# Blackbox_Brightness_Sensor_Schematic.net
KiCad netlist of a schematic drawn in Altium Designer
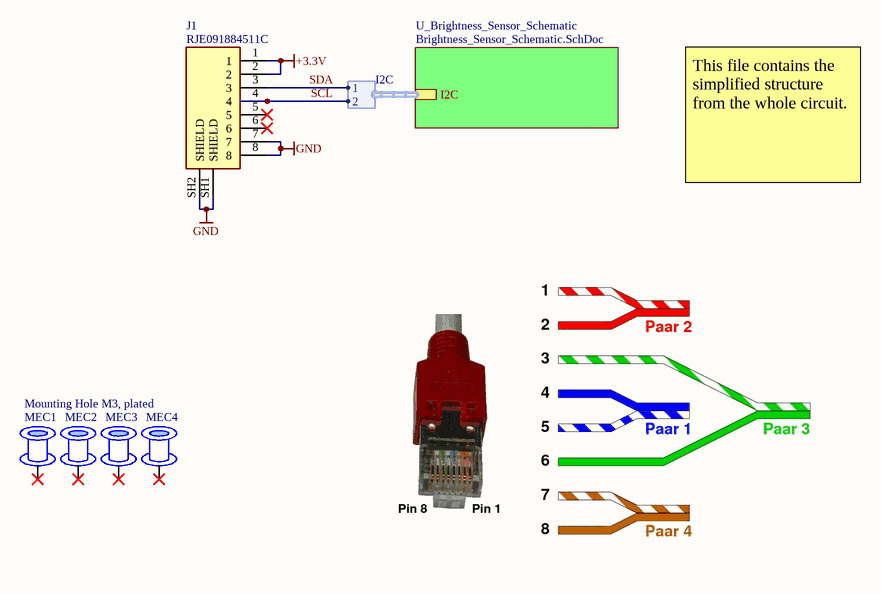
[diagram p0: Blackbox_Brightness_Sensor_Schematic.SchDoc]

(export (version "E")
  (design (tool "Eeschema 10.0.6"))
  (components
    (comp (ref "J1")
      (value "RJE091884511C")
      (footprint "PCB_Altium_Library_Manuel:RJ45")
      (description "Jack Modular Connector 8p8c (RJ45, Ethernet) 90Â° Angle (Right) Shielded Cat3.")
      (fields (field (name "MF") "Amphenol ICC (Commercial Products)"))
      (libsource (lib "Schematic_Altium_Library_Manuel") (part "RJ45"))
    )
    (comp (ref "MEC1")
      (value "Mounting Hole M3, plated")
      (footprint "PCB_Altium_Library_Manuel:Mounting Hole M3, plated")
      (description "Mounting Hole for M3 Screw, plated to connect signal")
      (libsource (lib "Schematic_Altium_Library_Manuel") (part "Mounting Hole M3, plated"))
    )
    (comp (ref "MEC2")
      (value "Mounting Hole M3, plated")
      (footprint "PCB_Altium_Library_Manuel:Mounting Hole M3, plated")
      (description "Mounting Hole for M3 Screw, plated to connect signal")
      (libsource (lib "Schematic_Altium_Library_Manuel") (part "Mounting Hole M3, plated"))
    )
    (comp (ref "MEC3")
      (value "Mounting Hole M3, plated")
      (footprint "PCB_Altium_Library_Manuel:Mounting Hole M3, plated")
      (description "Mounting Hole for M3 Screw, plated to connect signal")
      (libsource (lib "Schematic_Altium_Library_Manuel") (part "Mounting Hole M3, plated"))
    )
    (comp (ref "MEC4")
      (value "Mounting Hole M3, plated")
      (footprint "PCB_Altium_Library_Manuel:Mounting Hole M3, plated")
      (description "Mounting Hole for M3 Screw, plated to connect signal")
      (libsource (lib "Schematic_Altium_Library_Manuel") (part "Mounting Hole M3, plated"))
    )
  )
  (nets
    (net (code "2") (name "+3.3V") (class "Default")
      (node (ref "J1") (pin "1") (pinfunction "1_1") (pintype "passive"))
      (node (ref "J1") (pin "2") (pinfunction "2_2") (pintype "passive"))
    )
    (net (code "3") (name "/SCL") (class "Default")
      (node (ref "J1") (pin "4") (pinfunction "4_4") (pintype "passive"))
    )
    (net (code "4") (name "/SDA") (class "Default")
      (node (ref "J1") (pin "3") (pinfunction "3_3") (pintype "passive"))
    )
    (net (code "6") (name "GND") (class "Default")
      (node (ref "J1") (pin "7") (pinfunction "7_7") (pintype "passive"))
      (node (ref "J1") (pin "8") (pinfunction "8_8") (pintype "passive"))
      (node (ref "J1") (pin "SH1") (pinfunction "SHIELD_SH1") (pintype "passive"))
      (node (ref "J1") (pin "SH2") (pinfunction "SHIELD_SH2") (pintype "passive"))
    )
    (net (code "7") (name "unconnected-(J1-Pad5)") (class "Default")
      (node (ref "J1") (pin "5") (pinfunction "5_5") (pintype "passive+no_connect"))
    )
    (net (code "8") (name "unconnected-(J1-Pad6)") (class "Default")
      (node (ref "J1") (pin "6") (pinfunction "6_6") (pintype "passive+no_connect"))
    )
    (net (code "9") (name "unconnected-(MEC1-Pad1)") (class "Default")
      (node (ref "MEC1") (pin "1") (pinfunction "1_1") (pintype "passive+no_connect"))
    )
    (net (code "10") (name "unconnected-(MEC2-Pad1)") (class "Default")
      (node (ref "MEC2") (pin "1") (pinfunction "1_1") (pintype "passive+no_connect"))
    )
    (net (code "11") (name "unconnected-(MEC3-Pad1)") (class "Default")
      (node (ref "MEC3") (pin "1") (pinfunction "1_1") (pintype "passive+no_connect"))
    )
    (net (code "12") (name "unconnected-(MEC4-Pad1)") (class "Default")
      (node (ref "MEC4") (pin "1") (pinfunction "1_1") (pintype "passive+no_connect"))
    )
  )
)
